# driver.net
KiCad netlist of a schematic drawn in EAGLE
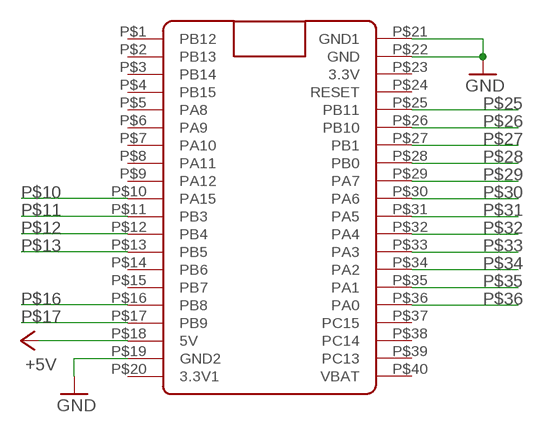
[diagram p0: schematic, sheet 1]
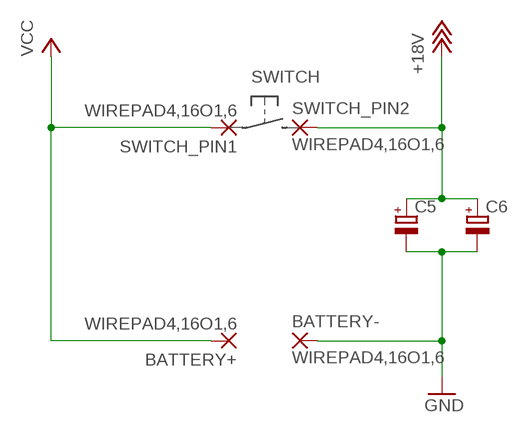
[diagram p1: schematic, sheet 2]
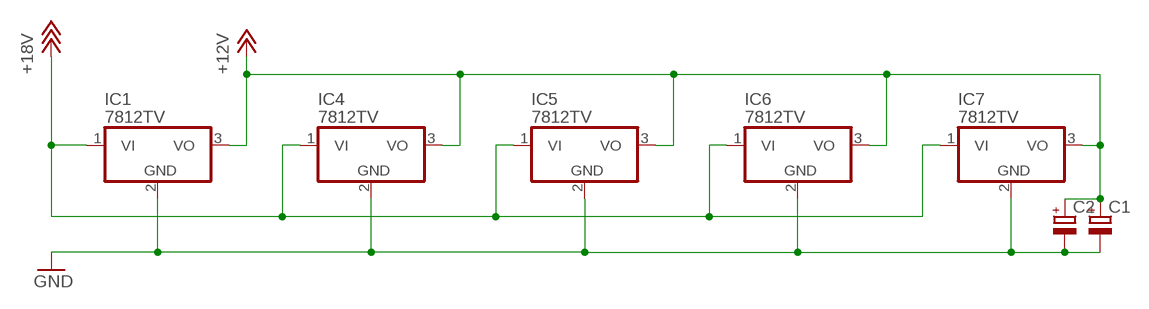
[diagram p2: schematic, sheet 3]
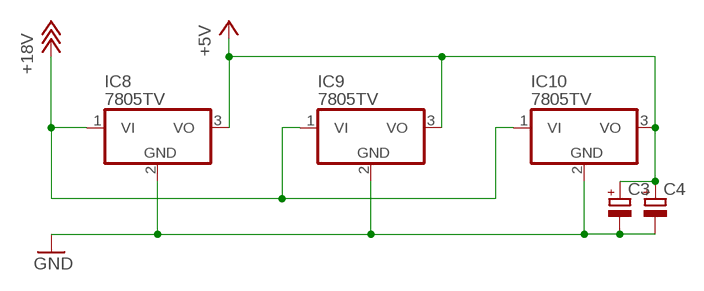
[diagram p3: schematic, sheet 4]
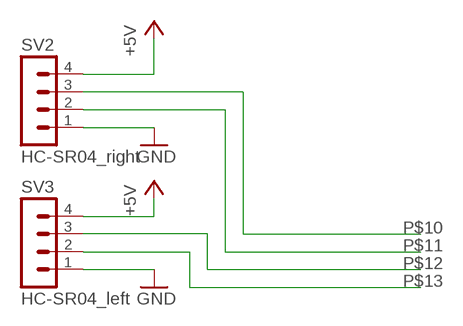
[diagram p4: schematic, sheet 5]
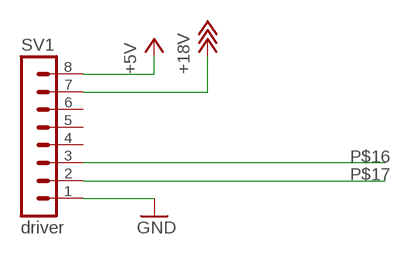
[diagram p5: schematic, sheet 6]
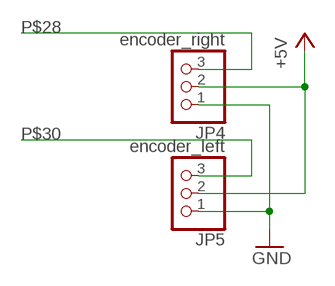
[diagram p6: schematic, sheet 7]
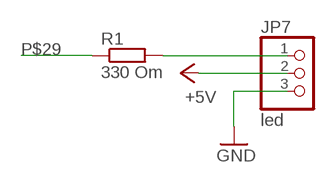
[diagram p7: schematic, sheet 8]
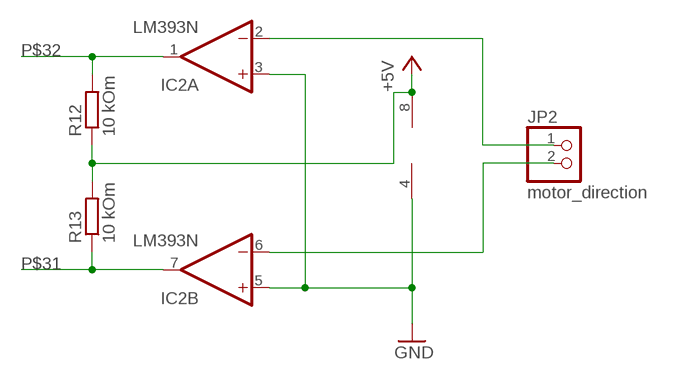
[diagram p8: schematic, sheet 9]
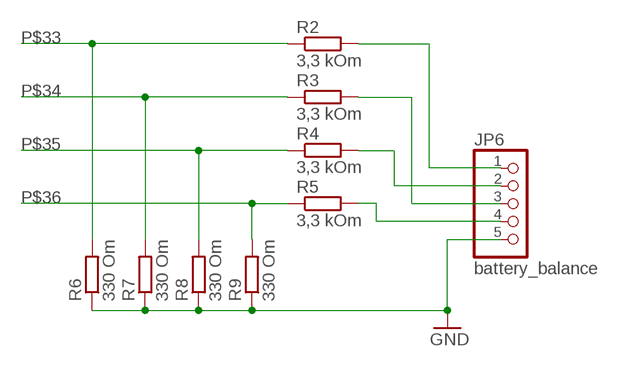
[diagram p9: schematic, sheet 10]
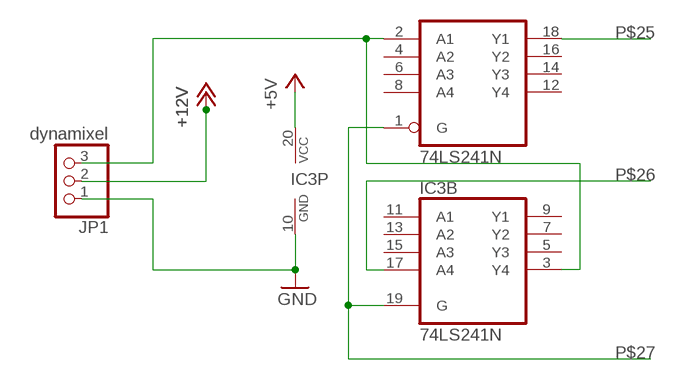
[diagram p10: schematic, sheet 11]

(export (version "E")
  (design (tool "Eeschema 10.0.6"))
  (components
    (comp (ref "C3")
      (value "CPOL-EUE2.5-5")
      (footprint "eagle-import:E2,5-5")
      (libsource (lib "eagle-import") (part "CPOL-EUE2.5-5"))
    )
    (comp (ref "C4")
      (value "CPOL-EUE5-8.5")
      (footprint "eagle-import:E5-8,5")
      (libsource (lib "eagle-import") (part "CPOL-EUE5-8.5"))
    )
    (comp (ref "IC8")
      (value "7805TV")
      (footprint "eagle-import:TO220V")
      (libsource (lib "eagle-import") (part "78TV05"))
    )
    (comp (ref "IC9")
      (value "7805TV")
      (footprint "eagle-import:TO220V")
      (libsource (lib "eagle-import") (part "78TV05"))
    )
    (comp (ref "IC10")
      (value "7805TV")
      (footprint "eagle-import:TO220V")
      (libsource (lib "eagle-import") (part "78TV05"))
    )
    (comp (ref "IC2")
      (value "LM393N")
      (footprint "eagle-import:DIL08")
      (libsource (lib "eagle-import") (part "LM393N"))
    )
    (comp (ref "JP2")
      (value "motor_direction")
      (footprint "eagle-import:1X02")
      (libsource (lib "eagle-import") (part "PINHD-1X2"))
    )
    (comp (ref "R12")
      (value "10 kOm")
      (footprint "eagle-import:0207_12")
      (libsource (lib "eagle-import") (part "R-EU_0207/12"))
    )
    (comp (ref "R13")
      (value "10 kOm")
      (footprint "eagle-import:0207_12")
      (libsource (lib "eagle-import") (part "R-EU_0207/12"))
    )
    (comp (ref "SV1")
      (value "driver")
      (footprint "eagle-import:MA08-1")
      (libsource (lib "eagle-import") (part "MA08-1"))
    )
    (comp (ref "IC3")
      (value "74LS241N")
      (footprint "eagle-import:DIL20")
      (libsource (lib "eagle-import") (part "74241NLS"))
    )
    (comp (ref "JP1")
      (value "dynamixel")
      (footprint "eagle-import:1X03")
      (libsource (lib "eagle-import") (part "PINHD-1X3"))
    )
    (comp (ref "C1")
      (value "CPOL-EUE5-8.5")
      (footprint "eagle-import:E5-8,5")
      (libsource (lib "eagle-import") (part "CPOL-EUE5-8.5"))
    )
    (comp (ref "C2")
      (value "CPOL-EUE2.5-5")
      (footprint "eagle-import:E2,5-5")
      (libsource (lib "eagle-import") (part "CPOL-EUE2.5-5"))
    )
    (comp (ref "IC1")
      (value "7812TV")
      (footprint "eagle-import:TO220V")
      (libsource (lib "eagle-import") (part "78TV12"))
    )
    (comp (ref "IC4")
      (value "7812TV")
      (footprint "eagle-import:TO220V")
      (libsource (lib "eagle-import") (part "78TV12"))
    )
    (comp (ref "IC5")
      (value "7812TV")
      (footprint "eagle-import:TO220V")
      (libsource (lib "eagle-import") (part "78TV12"))
    )
    (comp (ref "IC6")
      (value "7812TV")
      (footprint "eagle-import:TO220V")
      (libsource (lib "eagle-import") (part "78TV12"))
    )
    (comp (ref "IC7")
      (value "7812TV")
      (footprint "eagle-import:TO220V")
      (libsource (lib "eagle-import") (part "78TV12"))
    )
    (comp (ref "JP6")
      (value "battery_balance")
      (footprint "eagle-import:1_05X2MM")
      (libsource (lib "eagle-import") (part "PINHD-1X55X2MM"))
    )
    (comp (ref "R2")
      (value "3,3 kOm")
      (footprint "eagle-import:0207_15")
      (libsource (lib "eagle-import") (part "R-EU_0207/15"))
    )
    (comp (ref "R3")
      (value "3,3 kOm")
      (footprint "eagle-import:0207_15")
      (libsource (lib "eagle-import") (part "R-EU_0207/15"))
    )
    (comp (ref "R4")
      (value "3,3 kOm")
      (footprint "eagle-import:0207_15")
      (libsource (lib "eagle-import") (part "R-EU_0207/15"))
    )
    (comp (ref "R5")
      (value "3,3 kOm")
      (footprint "eagle-import:0207_15")
      (libsource (lib "eagle-import") (part "R-EU_0207/15"))
    )
    (comp (ref "R6")
      (value "330 Om")
      (footprint "eagle-import:0207_15")
      (libsource (lib "eagle-import") (part "R-EU_0207/15"))
    )
    (comp (ref "R7")
      (value "330 Om")
      (footprint "eagle-import:0207_15")
      (libsource (lib "eagle-import") (part "R-EU_0207/15"))
    )
    (comp (ref "R8")
      (value "330 Om")
      (footprint "eagle-import:0207_15")
      (libsource (lib "eagle-import") (part "R-EU_0207/15"))
    )
    (comp (ref "R9")
      (value "330 Om")
      (footprint "eagle-import:0207_15")
      (libsource (lib "eagle-import") (part "R-EU_0207/15"))
    )
    (comp (ref "JP4")
      (value "encoder_right")
      (footprint "eagle-import:1X03")
      (libsource (lib "eagle-import") (part "PINHD-1X3"))
    )
    (comp (ref "JP5")
      (value "encoder_left")
      (footprint "eagle-import:1X03")
      (libsource (lib "eagle-import") (part "PINHD-1X3"))
    )
    (comp (ref "JP7")
      (value "led")
      (footprint "eagle-import:1X03")
      (libsource (lib "eagle-import") (part "PINHD-1X3"))
    )
    (comp (ref "R1")
      (value "330 Om")
      (footprint "eagle-import:0207_12")
      (libsource (lib "eagle-import") (part "R-EU_0207/12"))
    )
    (comp (ref "BATTERY+")
      (value "WIREPAD4,16O1,6")
      (footprint "eagle-import:4,16O1,6")
      (libsource (lib "eagle-import") (part "WIREPAD4,16O1,6"))
    )
    (comp (ref "BATTERY-")
      (value "WIREPAD4,16O1,6")
      (footprint "eagle-import:4,16O1,6")
      (libsource (lib "eagle-import") (part "WIREPAD4,16O1,6"))
    )
    (comp (ref "C5")
      (value "CPOL-EUE5-8.5")
      (footprint "eagle-import:E5-8,5")
      (libsource (lib "eagle-import") (part "CPOL-EUE5-8.5"))
    )
    (comp (ref "C6")
      (value "CPOL-EUE2.5-5")
      (footprint "eagle-import:E2,5-5")
      (libsource (lib "eagle-import") (part "CPOL-EUE2.5-5"))
    )
    (comp (ref "SWITCH_PIN1")
      (value "WIREPAD4,16O1,6")
      (footprint "eagle-import:4,16O1,6")
      (libsource (lib "eagle-import") (part "WIREPAD4,16O1,6"))
    )
    (comp (ref "SWITCH_PIN2")
      (value "WIREPAD4,16O1,6")
      (footprint "eagle-import:4,16O1,6")
      (libsource (lib "eagle-import") (part "WIREPAD4,16O1,6"))
    )
    (comp (ref "SV2")
      (value "HC-SR04_right")
      (footprint "eagle-import:MA04-1")
      (libsource (lib "eagle-import") (part "MA04-1"))
    )
    (comp (ref "SV3")
      (value "HC-SR04_left")
      (footprint "eagle-import:MA04-1")
      (libsource (lib "eagle-import") (part "MA04-1"))
    )
    (comp (ref "U$1")
      (value "STM32F103C8T6")
      (footprint "eagle-import:BLUE_PILL_ADV")
      (libsource (lib "eagle-import") (part "BLUE_PILLADVANCED"))
    )
  )
  (nets
    (net (code "1") (name "+5V") (class "Default")
      (node (ref "C3") (pin "+") (pinfunction "+_+") (pintype "passive"))
      (node (ref "C4") (pin "+") (pinfunction "+_+") (pintype "passive"))
      (node (ref "IC10") (pin "3") (pinfunction "VO_3") (pintype "passive"))
      (node (ref "IC2") (pin "8") (pinfunction "V+_8") (pintype "power_in"))
      (node (ref "IC3") (pin "20") (pinfunction "VCC_20") (pintype "power_in"))
      (node (ref "IC8") (pin "3") (pinfunction "VO_3") (pintype "passive"))
      (node (ref "IC9") (pin "3") (pinfunction "VO_3") (pintype "passive"))
      (node (ref "JP4") (pin "2") (pinfunction "2_2") (pintype "passive"))
      (node (ref "JP5") (pin "2") (pinfunction "2_2") (pintype "passive"))
      (node (ref "JP7") (pin "2") (pinfunction "2_2") (pintype "passive"))
      (node (ref "R12") (pin "1") (pinfunction "1_1") (pintype "passive"))
      (node (ref "R13") (pin "2") (pinfunction "2_2") (pintype "passive"))
      (node (ref "SV1") (pin "8") (pinfunction "8_8") (pintype "passive"))
      (node (ref "SV2") (pin "4") (pinfunction "4_4") (pintype "passive"))
      (node (ref "SV3") (pin "4") (pinfunction "4_4") (pintype "passive"))
      (node (ref "U$1") (pin "P$18") (pinfunction "5V_P$18") (pintype "bidirectional"))
    )
    (net (code "2") (name "+12V") (class "Default")
      (node (ref "C1") (pin "+") (pinfunction "+_+") (pintype "passive"))
      (node (ref "C2") (pin "+") (pinfunction "+_+") (pintype "passive"))
      (node (ref "IC1") (pin "3") (pinfunction "VO_3") (pintype "passive"))
      (node (ref "IC4") (pin "3") (pinfunction "VO_3") (pintype "passive"))
      (node (ref "IC5") (pin "3") (pinfunction "VO_3") (pintype "passive"))
      (node (ref "IC6") (pin "3") (pinfunction "VO_3") (pintype "passive"))
      (node (ref "IC7") (pin "3") (pinfunction "VO_3") (pintype "passive"))
      (node (ref "JP1") (pin "2") (pinfunction "2_2") (pintype "passive"))
    )
    (net (code "3") (name "+18V") (class "Default")
      (node (ref "C5") (pin "+") (pinfunction "+_+") (pintype "passive"))
      (node (ref "C6") (pin "+") (pinfunction "+_+") (pintype "passive"))
      (node (ref "IC1") (pin "1") (pinfunction "VI_1") (pintype "input"))
      (node (ref "IC10") (pin "1") (pinfunction "VI_1") (pintype "input"))
      (node (ref "IC4") (pin "1") (pinfunction "VI_1") (pintype "input"))
      (node (ref "IC5") (pin "1") (pinfunction "VI_1") (pintype "input"))
      (node (ref "IC6") (pin "1") (pinfunction "VI_1") (pintype "input"))
      (node (ref "IC7") (pin "1") (pinfunction "VI_1") (pintype "input"))
      (node (ref "IC8") (pin "1") (pinfunction "VI_1") (pintype "input"))
      (node (ref "IC9") (pin "1") (pinfunction "VI_1") (pintype "input"))
      (node (ref "SV1") (pin "7") (pinfunction "7_7") (pintype "passive"))
      (node (ref "SWITCH_PIN2") (pin "1") (pinfunction "P_1") (pintype "passive"))
    )
    (net (code "4") (name "GND") (class "Default")
      (node (ref "BATTERY-") (pin "1") (pinfunction "P_1") (pintype "passive"))
      (node (ref "C1") (pin "-") (pinfunction "-_-") (pintype "passive"))
      (node (ref "C2") (pin "-") (pinfunction "-_-") (pintype "passive"))
      (node (ref "C3") (pin "-") (pinfunction "-_-") (pintype "passive"))
      (node (ref "C4") (pin "-") (pinfunction "-_-") (pintype "passive"))
      (node (ref "C5") (pin "-") (pinfunction "-_-") (pintype "passive"))
      (node (ref "C6") (pin "-") (pinfunction "-_-") (pintype "passive"))
      (node (ref "IC1") (pin "2") (pinfunction "GND_2") (pintype "passive"))
      (node (ref "IC10") (pin "2") (pinfunction "GND_2") (pintype "passive"))
      (node (ref "IC2") (pin "3") (pinfunction "+IN_3") (pintype "input"))
      (node (ref "IC2") (pin "4") (pinfunction "V-_4") (pintype "power_in"))
      (node (ref "IC2") (pin "5") (pinfunction "+IN_5") (pintype "input"))
      (node (ref "IC3") (pin "10") (pinfunction "GND_10") (pintype "power_in"))
      (node (ref "IC4") (pin "2") (pinfunction "GND_2") (pintype "passive"))
      (node (ref "IC5") (pin "2") (pinfunction "GND_2") (pintype "passive"))
      (node (ref "IC6") (pin "2") (pinfunction "GND_2") (pintype "passive"))
      (node (ref "IC7") (pin "2") (pinfunction "GND_2") (pintype "passive"))
      (node (ref "IC8") (pin "2") (pinfunction "GND_2") (pintype "passive"))
      (node (ref "IC9") (pin "2") (pinfunction "GND_2") (pintype "passive"))
      (node (ref "JP1") (pin "1") (pinfunction "1_1") (pintype "passive"))
      (node (ref "JP4") (pin "1") (pinfunction "1_1") (pintype "passive"))
      (node (ref "JP5") (pin "1") (pinfunction "1_1") (pintype "passive"))
      (node (ref "JP6") (pin "5") (pinfunction "5_5") (pintype "passive"))
      (node (ref "JP7") (pin "3") (pinfunction "3_3") (pintype "passive"))
      (node (ref "R6") (pin "1") (pinfunction "1_1") (pintype "passive"))
      (node (ref "R7") (pin "1") (pinfunction "1_1") (pintype "passive"))
      (node (ref "R8") (pin "1") (pinfunction "1_1") (pintype "passive"))
      (node (ref "R9") (pin "1") (pinfunction "1_1") (pintype "passive"))
      (node (ref "SV1") (pin "1") (pinfunction "1_1") (pintype "passive"))
      (node (ref "SV2") (pin "1") (pinfunction "1_1") (pintype "passive"))
      (node (ref "SV3") (pin "1") (pinfunction "1_1") (pintype "passive"))
      (node (ref "U$1") (pin "P$19") (pinfunction "GND2_P$19") (pintype "bidirectional"))
      (node (ref "U$1") (pin "P$21") (pinfunction "GND1_P$21") (pintype "power_in"))
      (node (ref "U$1") (pin "P$22") (pinfunction "GND_P$22") (pintype "bidirectional"))
    )
    (net (code "5") (name "Net-(IC2A--IN)") (class "Default")
      (node (ref "IC2") (pin "2") (pinfunction "-IN_2") (pintype "input"))
      (node (ref "JP2") (pin "1") (pinfunction "1_1") (pintype "passive"))
    )
    (net (code "6") (name "Net-(IC2B--IN)") (class "Default")
      (node (ref "IC2") (pin "6") (pinfunction "-IN_6") (pintype "input"))
      (node (ref "JP2") (pin "2") (pinfunction "2_2") (pintype "passive"))
    )
    (net (code "7") (name "Net-(IC3A-A1)") (class "Default")
      (node (ref "IC3") (pin "2") (pinfunction "A1_2") (pintype "input"))
      (node (ref "IC3") (pin "3") (pinfunction "Y4_3") (pintype "tri_state"))
      (node (ref "JP1") (pin "3") (pinfunction "3_3") (pintype "passive"))
    )
    (net (code "8") (name "Net-(JP6-Pad1)") (class "Default")
      (node (ref "JP6") (pin "1") (pinfunction "1_1") (pintype "passive"))
      (node (ref "R2") (pin "2") (pinfunction "2_2") (pintype "passive"))
    )
    (net (code "9") (name "Net-(JP6-Pad2)") (class "Default")
      (node (ref "JP6") (pin "2") (pinfunction "2_2") (pintype "passive"))
      (node (ref "R4") (pin "2") (pinfunction "2_2") (pintype "passive"))
    )
    (net (code "10") (name "Net-(JP6-Pad3)") (class "Default")
      (node (ref "JP6") (pin "3") (pinfunction "3_3") (pintype "passive"))
      (node (ref "R3") (pin "2") (pinfunction "2_2") (pintype "passive"))
    )
    (net (code "11") (name "Net-(JP6-Pad4)") (class "Default")
      (node (ref "JP6") (pin "4") (pinfunction "4_4") (pintype "passive"))
      (node (ref "R5") (pin "2") (pinfunction "2_2") (pintype "passive"))
    )
    (net (code "12") (name "Net-(JP7-Pad1)") (class "Default")
      (node (ref "JP7") (pin "1") (pinfunction "1_1") (pintype "passive"))
      (node (ref "R1") (pin "2") (pinfunction "2_2") (pintype "passive"))
    )
    (net (code "13") (name "P$10") (class "Default")
      (node (ref "SV2") (pin "3") (pinfunction "3_3") (pintype "passive"))
      (node (ref "U$1") (pin "P$10") (pinfunction "PA15_P$10") (pintype "bidirectional"))
    )
    (net (code "14") (name "P$11") (class "Default")
      (node (ref "SV2") (pin "2") (pinfunction "2_2") (pintype "passive"))
      (node (ref "U$1") (pin "P$11") (pinfunction "PB3_P$11") (pintype "bidirectional"))
    )
    (net (code "15") (name "P$12") (class "Default")
      (node (ref "SV3") (pin "3") (pinfunction "3_3") (pintype "passive"))
      (node (ref "U$1") (pin "P$12") (pinfunction "PB4_P$12") (pintype "bidirectional"))
    )
    (net (code "16") (name "P$13") (class "Default")
      (node (ref "SV3") (pin "2") (pinfunction "2_2") (pintype "passive"))
      (node (ref "U$1") (pin "P$13") (pinfunction "PB5_P$13") (pintype "bidirectional"))
    )
    (net (code "17") (name "P$16") (class "Default")
      (node (ref "SV1") (pin "3") (pinfunction "3_3") (pintype "passive"))
      (node (ref "U$1") (pin "P$16") (pinfunction "PB8_P$16") (pintype "bidirectional"))
    )
    (net (code "18") (name "P$17") (class "Default")
      (node (ref "SV1") (pin "2") (pinfunction "2_2") (pintype "passive"))
      (node (ref "U$1") (pin "P$17") (pinfunction "PB9_P$17") (pintype "bidirectional"))
    )
    (net (code "19") (name "P$25") (class "Default")
      (node (ref "IC3") (pin "18") (pinfunction "Y1_18") (pintype "tri_state"))
      (node (ref "U$1") (pin "P$25") (pinfunction "PB11_P$25") (pintype "bidirectional"))
    )
    (net (code "20") (name "P$26") (class "Default")
      (node (ref "IC3") (pin "17") (pinfunction "A4_17") (pintype "input"))
      (node (ref "U$1") (pin "P$26") (pinfunction "PB10_P$26") (pintype "bidirectional"))
    )
    (net (code "21") (name "P$27") (class "Default")
      (node (ref "IC3") (pin "1") (pinfunction "G_1") (pintype "input"))
      (node (ref "IC3") (pin "19") (pinfunction "G_19") (pintype "input"))
      (node (ref "U$1") (pin "P$27") (pinfunction "PB1_P$27") (pintype "bidirectional"))
    )
    (net (code "22") (name "P$28") (class "Default")
      (node (ref "JP4") (pin "3") (pinfunction "3_3") (pintype "passive"))
      (node (ref "U$1") (pin "P$28") (pinfunction "PB0_P$28") (pintype "bidirectional"))
    )
    (net (code "23") (name "P$29") (class "Default")
      (node (ref "R1") (pin "1") (pinfunction "1_1") (pintype "passive"))
      (node (ref "U$1") (pin "P$29") (pinfunction "PA7_P$29") (pintype "bidirectional"))
    )
    (net (code "24") (name "P$30") (class "Default")
      (node (ref "JP5") (pin "3") (pinfunction "3_3") (pintype "passive"))
      (node (ref "U$1") (pin "P$30") (pinfunction "PA6_P$30") (pintype "bidirectional"))
    )
    (net (code "25") (name "P$31") (class "Default")
      (node (ref "IC2") (pin "7") (pinfunction "OUT_7") (pintype "output"))
      (node (ref "R13") (pin "1") (pinfunction "1_1") (pintype "passive"))
      (node (ref "U$1") (pin "P$31") (pinfunction "PA5_P$31") (pintype "bidirectional"))
    )
    (net (code "26") (name "P$32") (class "Default")
      (node (ref "IC2") (pin "1") (pinfunction "OUT_1") (pintype "output"))
      (node (ref "R12") (pin "2") (pinfunction "2_2") (pintype "passive"))
      (node (ref "U$1") (pin "P$32") (pinfunction "PA4_P$32") (pintype "bidirectional"))
    )
    (net (code "27") (name "P$33") (class "Default")
      (node (ref "R2") (pin "1") (pinfunction "1_1") (pintype "passive"))
      (node (ref "R6") (pin "2") (pinfunction "2_2") (pintype "passive"))
      (node (ref "U$1") (pin "P$33") (pinfunction "PA3_P$33") (pintype "bidirectional"))
    )
    (net (code "28") (name "P$34") (class "Default")
      (node (ref "R3") (pin "1") (pinfunction "1_1") (pintype "passive"))
      (node (ref "R7") (pin "2") (pinfunction "2_2") (pintype "passive"))
      (node (ref "U$1") (pin "P$34") (pinfunction "PA2_P$34") (pintype "bidirectional"))
    )
    (net (code "29") (name "P$35") (class "Default")
      (node (ref "R4") (pin "1") (pinfunction "1_1") (pintype "passive"))
      (node (ref "R8") (pin "2") (pinfunction "2_2") (pintype "passive"))
      (node (ref "U$1") (pin "P$35") (pinfunction "PA1_P$35") (pintype "bidirectional"))
    )
    (net (code "30") (name "P$36") (class "Default")
      (node (ref "R5") (pin "1") (pinfunction "1_1") (pintype "passive"))
      (node (ref "R9") (pin "2") (pinfunction "2_2") (pintype "passive"))
      (node (ref "U$1") (pin "P$36") (pinfunction "PA0_P$36") (pintype "bidirectional"))
    )
    (net (code "31") (name "VCC") (class "Default")
      (node (ref "BATTERY+") (pin "1") (pinfunction "P_1") (pintype "passive"))
      (node (ref "SWITCH_PIN1") (pin "1") (pinfunction "P_1") (pintype "passive"))
    )
    (net (code "32") (name "unconnected-(IC3A-A2-Pad4)") (class "Default")
      (node (ref "IC3") (pin "4") (pinfunction "A2_4") (pintype "input"))
    )
    (net (code "33") (name "unconnected-(IC3A-A3-Pad6)") (class "Default")
      (node (ref "IC3") (pin "6") (pinfunction "A3_6") (pintype "input"))
    )
    (net (code "34") (name "unconnected-(IC3A-A4-Pad8)") (class "Default")
      (node (ref "IC3") (pin "8") (pinfunction "A4_8") (pintype "input"))
    )
    (net (code "35") (name "unconnected-(IC3A-Y2-Pad16)") (class "Default")
      (node (ref "IC3") (pin "16") (pinfunction "Y2_16") (pintype "tri_state"))
    )
    (net (code "36") (name "unconnected-(IC3A-Y3-Pad14)") (class "Default")
      (node (ref "IC3") (pin "14") (pinfunction "Y3_14") (pintype "tri_state"))
    )
    (net (code "37") (name "unconnected-(IC3A-Y4-Pad12)") (class "Default")
      (node (ref "IC3") (pin "12") (pinfunction "Y4_12") (pintype "tri_state"))
    )
    (net (code "38") (name "unconnected-(IC3B-A1-Pad11)") (class "Default")
      (node (ref "IC3") (pin "11") (pinfunction "A1_11") (pintype "input"))
    )
    (net (code "39") (name "unconnected-(IC3B-A2-Pad13)") (class "Default")
      (node (ref "IC3") (pin "13") (pinfunction "A2_13") (pintype "input"))
    )
    (net (code "40") (name "unconnected-(IC3B-A3-Pad15)") (class "Default")
      (node (ref "IC3") (pin "15") (pinfunction "A3_15") (pintype "input"))
    )
    (net (code "41") (name "unconnected-(IC3B-Y1-Pad9)") (class "Default")
      (node (ref "IC3") (pin "9") (pinfunction "Y1_9") (pintype "tri_state"))
    )
    (net (code "42") (name "unconnected-(IC3B-Y2-Pad7)") (class "Default")
      (node (ref "IC3") (pin "7") (pinfunction "Y2_7") (pintype "tri_state"))
    )
    (net (code "43") (name "unconnected-(IC3B-Y3-Pad5)") (class "Default")
      (node (ref "IC3") (pin "5") (pinfunction "Y3_5") (pintype "tri_state"))
    )
    (net (code "44") (name "unconnected-(SV1-Pad4)") (class "Default")
      (node (ref "SV1") (pin "4") (pinfunction "4_4") (pintype "passive"))
    )
    (net (code "45") (name "unconnected-(SV1-Pad5)") (class "Default")
      (node (ref "SV1") (pin "5") (pinfunction "5_5") (pintype "passive"))
    )
    (net (code "46") (name "unconnected-(SV1-Pad6)") (class "Default")
      (node (ref "SV1") (pin "6") (pinfunction "6_6") (pintype "passive"))
    )
    (net (code "47") (name "unconnected-(U$1-3.3V-PadP$23)") (class "Default")
      (node (ref "U$1") (pin "P$23") (pinfunction "3.3V_P$23") (pintype "bidirectional"))
    )
    (net (code "48") (name "unconnected-(U$1-3.3V1-PadP$20)") (class "Default")
      (node (ref "U$1") (pin "P$20") (pinfunction "3.3V1_P$20") (pintype "bidirectional"))
    )
    (net (code "49") (name "unconnected-(U$1-PA8-PadP$5)") (class "Default")
      (node (ref "U$1") (pin "P$5") (pinfunction "PA8_P$5") (pintype "bidirectional"))
    )
    (net (code "50") (name "unconnected-(U$1-PA9-PadP$6)") (class "Default")
      (node (ref "U$1") (pin "P$6") (pinfunction "PA9_P$6") (pintype "bidirectional"))
    )
    (net (code "51") (name "unconnected-(U$1-PA10-PadP$7)") (class "Default")
      (node (ref "U$1") (pin "P$7") (pinfunction "PA10_P$7") (pintype "bidirectional"))
    )
    (net (code "52") (name "unconnected-(U$1-PA11-PadP$8)") (class "Default")
      (node (ref "U$1") (pin "P$8") (pinfunction "PA11_P$8") (pintype "bidirectional"))
    )
    (net (code "53") (name "unconnected-(U$1-PA12-PadP$9)") (class "Default")
      (node (ref "U$1") (pin "P$9") (pinfunction "PA12_P$9") (pintype "bidirectional"))
    )
    (net (code "54") (name "unconnected-(U$1-PB6-PadP$14)") (class "Default")
      (node (ref "U$1") (pin "P$14") (pinfunction "PB6_P$14") (pintype "bidirectional"))
    )
    (net (code "55") (name "unconnected-(U$1-PB7-PadP$15)") (class "Default")
      (node (ref "U$1") (pin "P$15") (pinfunction "PB7_P$15") (pintype "bidirectional"))
    )
    (net (code "56") (name "unconnected-(U$1-PB12-PadP$1)") (class "Default")
      (node (ref "U$1") (pin "P$1") (pinfunction "PB12_P$1") (pintype "bidirectional"))
    )
    (net (code "57") (name "unconnected-(U$1-PB13-PadP$2)") (class "Default")
      (node (ref "U$1") (pin "P$2") (pinfunction "PB13_P$2") (pintype "bidirectional"))
    )
    (net (code "58") (name "unconnected-(U$1-PB14-PadP$3)") (class "Default")
      (node (ref "U$1") (pin "P$3") (pinfunction "PB14_P$3") (pintype "bidirectional"))
    )
    (net (code "59") (name "unconnected-(U$1-PB15-PadP$4)") (class "Default")
      (node (ref "U$1") (pin "P$4") (pinfunction "PB15_P$4") (pintype "bidirectional"))
    )
    (net (code "60") (name "unconnected-(U$1-PC13-PadP$39)") (class "Default")
      (node (ref "U$1") (pin "P$39") (pinfunction "PC13_P$39") (pintype "bidirectional"))
    )
    (net (code "61") (name "unconnected-(U$1-PC14-PadP$38)") (class "Default")
      (node (ref "U$1") (pin "P$38") (pinfunction "PC14_P$38") (pintype "bidirectional"))
    )
    (net (code "62") (name "unconnected-(U$1-PC15-PadP$37)") (class "Default")
      (node (ref "U$1") (pin "P$37") (pinfunction "PC15_P$37") (pintype "bidirectional"))
    )
    (net (code "63") (name "unconnected-(U$1-RESET-PadP$24)") (class "Default")
      (node (ref "U$1") (pin "P$24") (pinfunction "RESET_P$24") (pintype "bidirectional"))
    )
    (net (code "64") (name "unconnected-(U$1-VBAT-PadP$40)") (class "Default")
      (node (ref "U$1") (pin "P$40") (pinfunction "VBAT_P$40") (pintype "bidirectional"))
    )
  )
)
